# tape64v2.net
KiCad netlist of a schematic drawn in EAGLE
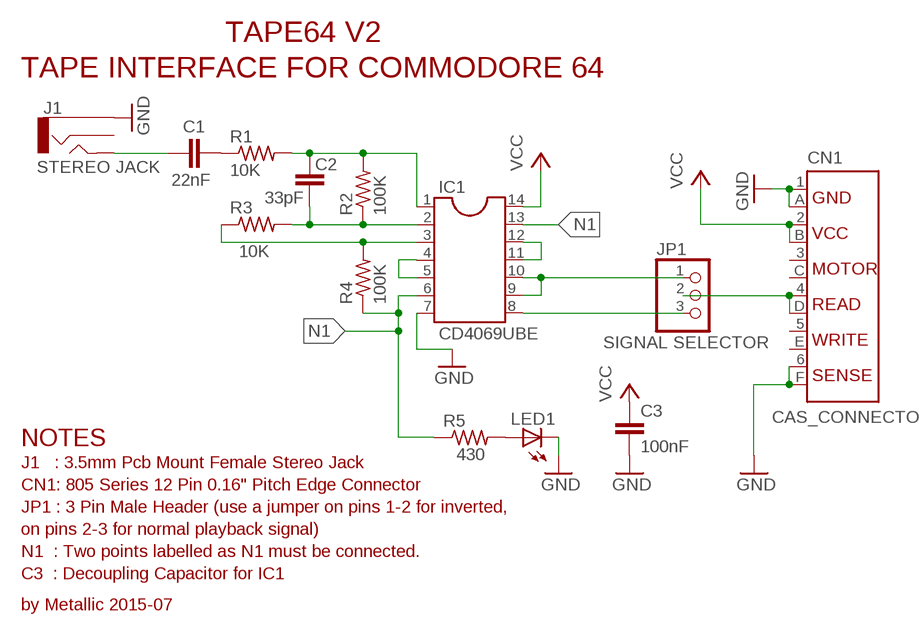
[diagram p0: schematic, sheet 1]

(export (version "E")
  (design (tool "Eeschema 10.0.6"))
  (components
    (comp (ref "C1")
      (value "22nF")
      (footprint "eagle-import:C050-025X075")
      (libsource (lib "eagle-import") (part "C-EU050-025X075"))
    )
    (comp (ref "C2")
      (value "33pF")
      (footprint "eagle-import:C025-024X044")
      (libsource (lib "eagle-import") (part "C-EU025-024X044"))
    )
    (comp (ref "C3")
      (value "100nF")
      (footprint "eagle-import:C050-035X075")
      (libsource (lib "eagle-import") (part "C-EU050-035X075"))
    )
    (comp (ref "CN1")
      (value "CAS_CONNECTOR")
      (footprint "eagle-import:CAS_CON")
      (libsource (lib "eagle-import") (part "CAS_CON"))
    )
    (comp (ref "IC1")
      (value "CD4069UBE")
      (footprint "eagle-import:DIL14")
      (libsource (lib "eagle-import") (part "DIL14"))
    )
    (comp (ref "J1")
      (value "STEREO JACK")
      (footprint "eagle-import:AUDIO-JACK")
      (libsource (lib "eagle-import") (part "AUDIO-JACKPTH"))
    )
    (comp (ref "JP1")
      (value "SIGNAL SELECTOR")
      (footprint "eagle-import:1X03")
      (libsource (lib "eagle-import") (part "PINHD-1X3"))
    )
    (comp (ref "LED1")
      (value "LED3MM")
      (footprint "eagle-import:LED3MM")
      (libsource (lib "eagle-import") (part "LED3MM"))
    )
    (comp (ref "R1")
      (value "10K")
      (footprint "eagle-import:0207_10")
      (libsource (lib "eagle-import") (part "R-US_0207/10"))
    )
    (comp (ref "R2")
      (value "100K")
      (footprint "eagle-import:0207_10")
      (libsource (lib "eagle-import") (part "R-US_0207/10"))
    )
    (comp (ref "R3")
      (value "10K")
      (footprint "eagle-import:0207_10")
      (libsource (lib "eagle-import") (part "R-US_0207/10"))
    )
    (comp (ref "R4")
      (value "100K")
      (footprint "eagle-import:0207_10")
      (libsource (lib "eagle-import") (part "R-US_0207/10"))
    )
    (comp (ref "R5")
      (value "430")
      (footprint "eagle-import:0207_10")
      (libsource (lib "eagle-import") (part "R-US_0207/10"))
    )
  )
  (nets
    (net (code "1") (name "GND") (class "Default")
      (node (ref "C3") (pin "2") (pinfunction "2_2") (pintype "passive"))
      (node (ref "CN1") (pin "1") (pinfunction "GND1_1") (pintype "passive"))
      (node (ref "CN1") (pin "6") (pinfunction "SENSE1_6") (pintype "input"))
      (node (ref "CN1") (pin "A") (pinfunction "GND2_A") (pintype "passive"))
      (node (ref "CN1") (pin "F") (pinfunction "SENSE2_F") (pintype "input"))
      (node (ref "IC1") (pin "7") (pinfunction "7_7") (pintype "passive"))
      (node (ref "J1") (pin "1") (pinfunction "1_1") (pintype "bidirectional"))
      (node (ref "LED1") (pin "K") (pinfunction "C_K") (pintype "passive"))
    )
    (net (code "2") (name "N1") (class "Default")
      (node (ref "IC1") (pin "13") (pinfunction "13_13") (pintype "passive"))
      (node (ref "IC1") (pin "6") (pinfunction "6_6") (pintype "passive"))
      (node (ref "R4") (pin "1") (pinfunction "1_1") (pintype "passive"))
      (node (ref "R5") (pin "1") (pinfunction "1_1") (pintype "passive"))
    )
    (net (code "3") (name "Net-(C1-Pad1)") (class "Default")
      (node (ref "C1") (pin "1") (pinfunction "1_1") (pintype "passive"))
      (node (ref "J1") (pin "5") (pinfunction "5_5") (pintype "bidirectional"))
    )
    (net (code "4") (name "Net-(C1-Pad2)") (class "Default")
      (node (ref "C1") (pin "2") (pinfunction "2_2") (pintype "passive"))
      (node (ref "R1") (pin "1") (pinfunction "1_1") (pintype "passive"))
    )
    (net (code "5") (name "Net-(C2-Pad1)") (class "Default")
      (node (ref "C2") (pin "1") (pinfunction "1_1") (pintype "passive"))
      (node (ref "IC1") (pin "2") (pinfunction "2_2") (pintype "passive"))
      (node (ref "R2") (pin "1") (pinfunction "1_1") (pintype "passive"))
      (node (ref "R3") (pin "2") (pinfunction "2_2") (pintype "passive"))
    )
    (net (code "6") (name "Net-(C2-Pad2)") (class "Default")
      (node (ref "C2") (pin "2") (pinfunction "2_2") (pintype "passive"))
      (node (ref "IC1") (pin "1") (pinfunction "1_1") (pintype "passive"))
      (node (ref "R1") (pin "2") (pinfunction "2_2") (pintype "passive"))
      (node (ref "R2") (pin "2") (pinfunction "2_2") (pintype "passive"))
    )
    (net (code "7") (name "Net-(CN1-READ1)") (class "Default")
      (node (ref "CN1") (pin "4") (pinfunction "READ1_4") (pintype "input"))
      (node (ref "CN1") (pin "D") (pinfunction "READ2_D") (pintype "input"))
      (node (ref "JP1") (pin "2") (pinfunction "2_2") (pintype "passive"))
    )
    (net (code "8") (name "Net-(IC1-Pad3)") (class "Default")
      (node (ref "IC1") (pin "3") (pinfunction "3_3") (pintype "passive"))
      (node (ref "R3") (pin "1") (pinfunction "1_1") (pintype "passive"))
      (node (ref "R4") (pin "2") (pinfunction "2_2") (pintype "passive"))
    )
    (net (code "9") (name "Net-(IC1-Pad4)") (class "Default")
      (node (ref "IC1") (pin "4") (pinfunction "4_4") (pintype "passive"))
      (node (ref "IC1") (pin "5") (pinfunction "5_5") (pintype "passive"))
    )
    (net (code "10") (name "Net-(IC1-Pad8)") (class "Default")
      (node (ref "IC1") (pin "8") (pinfunction "8_8") (pintype "passive"))
      (node (ref "JP1") (pin "3") (pinfunction "3_3") (pintype "passive"))
    )
    (net (code "11") (name "Net-(IC1-Pad10)") (class "Default")
      (node (ref "IC1") (pin "10") (pinfunction "10_10") (pintype "passive"))
      (node (ref "IC1") (pin "9") (pinfunction "9_9") (pintype "passive"))
      (node (ref "JP1") (pin "1") (pinfunction "1_1") (pintype "passive"))
    )
    (net (code "12") (name "Net-(IC1-Pad11)") (class "Default")
      (node (ref "IC1") (pin "11") (pinfunction "11_11") (pintype "passive"))
      (node (ref "IC1") (pin "12") (pinfunction "12_12") (pintype "passive"))
    )
    (net (code "13") (name "Net-(LED1-PadA)") (class "Default")
      (node (ref "LED1") (pin "A") (pinfunction "A_A") (pintype "passive"))
      (node (ref "R5") (pin "2") (pinfunction "2_2") (pintype "passive"))
    )
    (net (code "14") (name "VCC") (class "Default")
      (node (ref "C3") (pin "1") (pinfunction "1_1") (pintype "passive"))
      (node (ref "CN1") (pin "2") (pinfunction "VCC1_2") (pintype "passive"))
      (node (ref "CN1") (pin "B") (pinfunction "VCC2_B") (pintype "passive"))
      (node (ref "IC1") (pin "14") (pinfunction "14_14") (pintype "passive"))
    )
    (net (code "15") (name "unconnected-(CN1-MOTOR1-Pad3)") (class "Default")
      (node (ref "CN1") (pin "3") (pinfunction "MOTOR1_3") (pintype "passive"))
    )
    (net (code "16") (name "unconnected-(CN1-MOTOR2-PadC)") (class "Default")
      (node (ref "CN1") (pin "C") (pinfunction "MOTOR2_C") (pintype "passive"))
    )
    (net (code "17") (name "unconnected-(CN1-WRITE1-Pad5)") (class "Default")
      (node (ref "CN1") (pin "5") (pinfunction "WRITE1_5") (pintype "output"))
    )
    (net (code "18") (name "unconnected-(CN1-WRITE2-PadE)") (class "Default")
      (node (ref "CN1") (pin "E") (pinfunction "WRITE2_E") (pintype "output"))
    )
    (net (code "19") (name "unconnected-(J1-Pad2)") (class "Default")
      (node (ref "J1") (pin "2") (pinfunction "2_2") (pintype "bidirectional"))
    )
  )
)
